# 7segments.net
KiCad netlist of a schematic drawn in Altium Designer
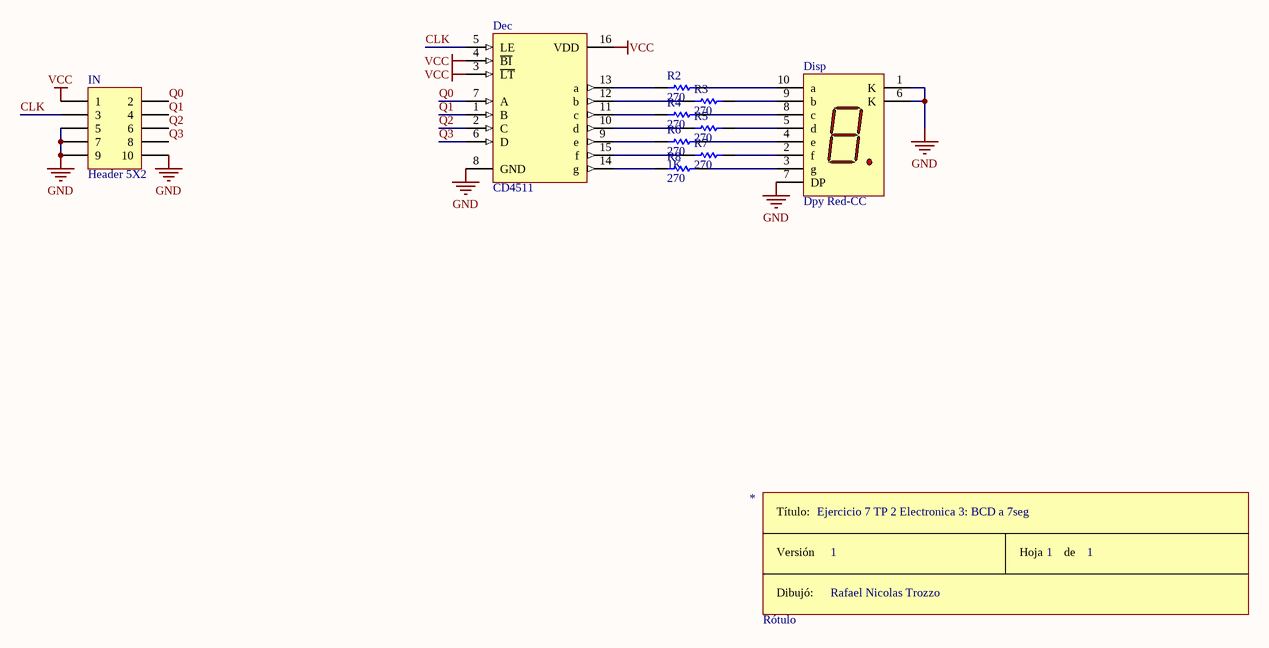
[diagram p0: 7segments.SchDoc]

(export (version "E")
  (design (tool "Eeschema 10.0.6"))
  (components
    (comp (ref "*") (value "Rótulo") (libsource (lib "LIB PIO IX") (part "Rótulo")))
    (comp (ref "Dec")
      (value "CD4511")
      (footprint "DIP16")
      (description "BCD to 7 SEGMENTOS")
      (libsource (lib "LIBEBAL") (part "CD4511"))
    )
    (comp (ref "Disp")
      (value "Dpy Red-CC")
      (footprint "A")
      (description "7.62 mm Black Surface HER 7-Segment Display: CC, RH DP")
      (fields (field (name "PUBLISHER") "Altium Limited"))
      (libsource (lib "Miscellaneous Devices") (part "Dpy Red-CC"))
    )
    (comp (ref "IN")
      (value "Header 5X2")
      (footprint "HDR2X5")
      (description "Header, 5-Pin, Dual row")
      (fields (field (name "PUBLISHER") "Altium Limited"))
      (libsource (lib "Miscellaneous Connectors") (part "Header 5X2"))
    )
    (comp (ref "R2")
      (value "270")
      (footprint "AXIAL-0.3")
      (description "Resistor")
      (fields (field (name "PUBLISHER") "Altium Limited"))
      (libsource (lib "Miscellaneous Devices") (part "Res1"))
    )
    (comp (ref "R3")
      (value "270")
      (footprint "AXIAL-0.3")
      (description "Resistor")
      (fields (field (name "PUBLISHER") "Altium Limited"))
      (libsource (lib "Miscellaneous Devices") (part "Res1"))
    )
    (comp (ref "R4")
      (value "270")
      (footprint "AXIAL-0.3")
      (description "Resistor")
      (fields (field (name "PUBLISHER") "Altium Limited"))
      (libsource (lib "Miscellaneous Devices") (part "Res1"))
    )
    (comp (ref "R5")
      (value "270")
      (footprint "AXIAL-0.3")
      (description "Resistor")
      (fields (field (name "PUBLISHER") "Altium Limited"))
      (libsource (lib "Miscellaneous Devices") (part "Res1"))
    )
    (comp (ref "R6")
      (value "270")
      (footprint "AXIAL-0.3")
      (description "Resistor")
      (fields (field (name "ALTIUM_VALUE") "1K") (field (name "PUBLISHER") "Altium Limited"))
      (libsource (lib "Miscellaneous Devices") (part "Res1"))
    )
    (comp (ref "R7")
      (value "270")
      (footprint "AXIAL-0.3")
      (description "Resistor")
      (fields (field (name "PUBLISHER") "Altium Limited"))
      (libsource (lib "Miscellaneous Devices") (part "Res1"))
    )
    (comp (ref "R8")
      (value "270")
      (footprint "AXIAL-0.3")
      (description "Resistor")
      (fields (field (name "PUBLISHER") "Altium Limited"))
      (libsource (lib "Miscellaneous Devices") (part "Res1"))
    )
  )
  (nets
    (net (code "1") (name "/CLK") (class "Default")
      (node (ref "Dec") (pin "5") (pinfunction "LE_5") (pintype "input"))
      (node (ref "IN") (pin "3") (pinfunction "3_3") (pintype "passive"))
    )
    (net (code "2") (name "/Q0") (class "Default")
      (node (ref "Dec") (pin "7") (pinfunction "A_7") (pintype "input"))
      (node (ref "IN") (pin "2") (pinfunction "2_2") (pintype "passive"))
    )
    (net (code "3") (name "/Q1") (class "Default")
      (node (ref "Dec") (pin "1") (pinfunction "B_1") (pintype "input"))
      (node (ref "IN") (pin "4") (pinfunction "4_4") (pintype "passive"))
    )
    (net (code "4") (name "/Q2") (class "Default")
      (node (ref "Dec") (pin "2") (pinfunction "C_2") (pintype "input"))
      (node (ref "IN") (pin "6") (pinfunction "6_6") (pintype "passive"))
    )
    (net (code "5") (name "/Q3") (class "Default")
      (node (ref "Dec") (pin "6") (pinfunction "D_6") (pintype "input"))
      (node (ref "IN") (pin "8") (pinfunction "8_8") (pintype "passive"))
    )
    (net (code "6") (name "GND") (class "Default")
      (node (ref "Dec") (pin "8") (pinfunction "GND_8") (pintype "power_in"))
      (node (ref "Disp") (pin "1") (pinfunction "K_1") (pintype "passive"))
      (node (ref "Disp") (pin "6") (pinfunction "K_6") (pintype "passive"))
      (node (ref "Disp") (pin "7") (pinfunction "DP_7") (pintype "passive"))
      (node (ref "IN") (pin "10") (pinfunction "10_10") (pintype "passive"))
      (node (ref "IN") (pin "5") (pinfunction "5_5") (pintype "passive"))
      (node (ref "IN") (pin "7") (pinfunction "7_7") (pintype "passive"))
      (node (ref "IN") (pin "9") (pinfunction "9_9") (pintype "passive"))
    )
    (net (code "7") (name "Net-(Dec-a)") (class "Default")
      (node (ref "Dec") (pin "13") (pinfunction "a_13") (pintype "output"))
      (node (ref "R2") (pin "1") (pinfunction "1_1") (pintype "passive"))
    )
    (net (code "8") (name "Net-(Dec-b)") (class "Default")
      (node (ref "Dec") (pin "12") (pinfunction "b_12") (pintype "output"))
      (node (ref "R3") (pin "1") (pinfunction "1_1") (pintype "passive"))
    )
    (net (code "9") (name "Net-(Dec-c)") (class "Default")
      (node (ref "Dec") (pin "11") (pinfunction "c_11") (pintype "output"))
      (node (ref "R4") (pin "1") (pinfunction "1_1") (pintype "passive"))
    )
    (net (code "10") (name "Net-(Dec-d)") (class "Default")
      (node (ref "Dec") (pin "10") (pinfunction "d_10") (pintype "output"))
      (node (ref "R5") (pin "1") (pinfunction "1_1") (pintype "passive"))
    )
    (net (code "11") (name "Net-(Dec-e)") (class "Default")
      (node (ref "Dec") (pin "9") (pinfunction "e_9") (pintype "output"))
      (node (ref "R6") (pin "1") (pinfunction "1_1") (pintype "passive"))
    )
    (net (code "12") (name "Net-(Dec-f)") (class "Default")
      (node (ref "Dec") (pin "15") (pinfunction "f_15") (pintype "output"))
      (node (ref "R7") (pin "1") (pinfunction "1_1") (pintype "passive"))
    )
    (net (code "13") (name "Net-(Dec-g)") (class "Default")
      (node (ref "Dec") (pin "14") (pinfunction "g_14") (pintype "output"))
      (node (ref "R8") (pin "1") (pinfunction "1_1") (pintype "passive"))
    )
    (net (code "14") (name "Net-(Disp-a)") (class "Default")
      (node (ref "Disp") (pin "10") (pinfunction "a_10") (pintype "passive"))
      (node (ref "R2") (pin "2") (pinfunction "2_2") (pintype "passive"))
    )
    (net (code "15") (name "Net-(Disp-b)") (class "Default")
      (node (ref "Disp") (pin "9") (pinfunction "b_9") (pintype "passive"))
      (node (ref "R3") (pin "2") (pinfunction "2_2") (pintype "passive"))
    )
    (net (code "16") (name "Net-(Disp-c)") (class "Default")
      (node (ref "Disp") (pin "8") (pinfunction "c_8") (pintype "passive"))
      (node (ref "R4") (pin "2") (pinfunction "2_2") (pintype "passive"))
    )
    (net (code "17") (name "Net-(Disp-d)") (class "Default")
      (node (ref "Disp") (pin "5") (pinfunction "d_5") (pintype "passive"))
      (node (ref "R5") (pin "2") (pinfunction "2_2") (pintype "passive"))
    )
    (net (code "18") (name "Net-(Disp-e)") (class "Default")
      (node (ref "Disp") (pin "4") (pinfunction "e_4") (pintype "passive"))
      (node (ref "R6") (pin "2") (pinfunction "2_2") (pintype "passive"))
    )
    (net (code "19") (name "Net-(Disp-f)") (class "Default")
      (node (ref "Disp") (pin "2") (pinfunction "f_2") (pintype "passive"))
      (node (ref "R7") (pin "2") (pinfunction "2_2") (pintype "passive"))
    )
    (net (code "20") (name "Net-(Disp-g)") (class "Default")
      (node (ref "Disp") (pin "3") (pinfunction "g_3") (pintype "passive"))
      (node (ref "R8") (pin "2") (pinfunction "2_2") (pintype "passive"))
    )
    (net (code "21") (name "VCC") (class "Default")
      (node (ref "Dec") (pin "16") (pinfunction "VDD_16") (pintype "power_in"))
      (node (ref "Dec") (pin "3") (pinfunction "~{LT}_3") (pintype "input"))
      (node (ref "Dec") (pin "4") (pinfunction "~{BI}_4") (pintype "input"))
      (node (ref "IN") (pin "1") (pinfunction "1_1") (pintype "passive"))
    )
  )
)
